# BQ_chip.net
KiCad netlist of a schematic drawn in Altium Designer
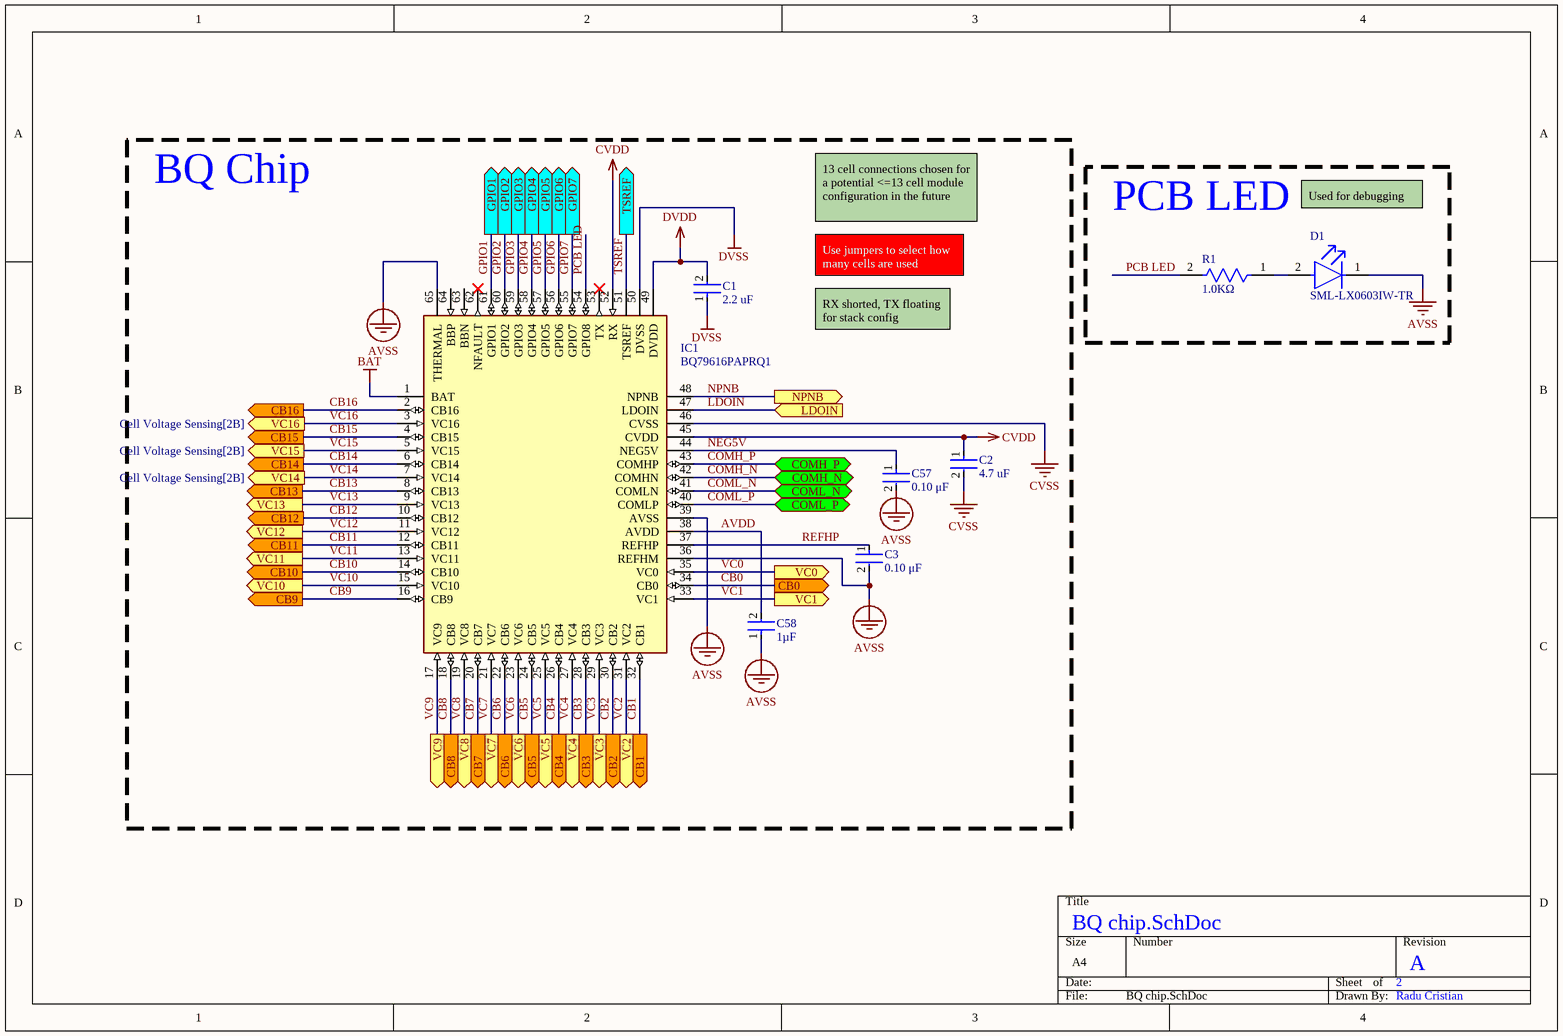
[diagram p0: BQ chip.SchDoc]

(export (version "E")
  (design (tool "Eeschema 10.0.6"))
  (components
    (comp (ref "C1")
      (value "CC0603KPX7R6BB225")
      (footprint "FP-CC0603-DA-MFG")
      (description "CC0603 2.2 uF X7R 10.00% 10 V")
      (fields
        (field (name "OCTOPART") "https://octopart.com/cc0603kpx7r6bb225-yageo-88116733")
        (field (name "TOLERANCE") "0.1")
        (field (name "CAPACITANCE") "2.2 uF")
      )
      (libsource (lib "Altium Content Vault") (part "11868f565c42a9108669ba33697ecf6"))
    )
    (comp (ref "C2")
      (value "CC0603KRX5R7BB475")
      (footprint "FP-CC0603-DA-MFG")
      (description "CAP CER 4.7UF 16V X5R 0603")
      (fields
        (field (name "MANUFACTURER") "YAGEO")
        (field (name "VOLTAGE") "16 V")
        (field (name "CAPACITANCE") "4.7 uF")
      )
      (libsource (lib "Altium Content Vault") (part "11868f565c42a9108669ba33697ecf6"))
    )
    (comp (ref "C3")
      (value "0.10 μF")
      (footprint "FP-C0603C-CF-MFG")
      (description "C0603 0.10 μF X7R 30ppm/°C 5.00% 50 V")
      (fields
        (field (name "MANUFACTURER") "KEMET")
        (field (name "MANUFACTURER PART NUMBER") "C0603C104J5RAC")
      )
      (libsource (lib "Altium Content Vault") (part "b4654b650e69147ec39a6b967a45e02"))
    )
    (comp (ref "C57")
      (value "0.10 μF")
      (footprint "FP-C0603C-CF-MFG")
      (description "C0603 0.10 μF X7R 30ppm/°C 5.00% 50 V")
      (fields
        (field (name "MANUFACTURER") "KEMET")
        (field (name "MANUFACTURER PART NUMBER") "C0603C104J5RAC")
      )
      (libsource (lib "Altium Content Vault") (part "b4654b650e69147ec39a6b967a45e02"))
    )
    (comp (ref "C58")
      (value "VJ0603Y105KXJCW1BC")
      (footprint "FP-VJ0603Y105KXJCW1BC-MFG")
      (description "VJ0603Y105KXJCW1BC Multilayer Ceramic Capacitor, 1 uF, 16 V, ± 10%, X7R, 0603 [1608 Metric]")
      (fields (field (name "CAPACITANCE") "1µF") (field (name "TOLERANCE") "10%"))
      (libsource (lib "Altium Content Vault") (part "b4654b650e69147ec39a6b967a45e02"))
    )
    (comp (ref "D1")
      (value "SML-LX0603IW-TR")
      (footprint "FP-SML-LX0603IW-TR-MFG")
      (description "LED RED DIFFUSED SMD")
      (libsource (lib "Altium Content Vault") (part "8706943c75ba83719d021d2fdc84c58"))
    )
    (comp (ref "IC1")
      (value "BQ79616PAPRQ1")
      (footprint "PcbLib1:QFP50P1200X1200X120-65N")
      (fields (field (name "MOUSER PART NUMBER") "595-BQ79616PAPRQ1"))
      (libsource (lib "Schlib1") (part "BQ79616PAPRQ1"))
    )
    (comp (ref "R1")
      (value "CPF0603F1K0C1")
      (footprint "FP-CPF0603-MFG")
      (description "RES SMD 1.0KΩ 1% 1/16W 0603")
      (fields
        (field (name "OCTOPART") "https://octopart.com/cpf0603f1k0c1-te+connectivity-42013134")
        (field (name "TOLERANCE") "1%")
        (field (name "RESISTANCE") "1.0KΩ")
      )
      (libsource (lib "Altium Content Vault") (part "1029c3af85768c4190bb7ad29bc67b5"))
    )
  )
  (nets
    (net (code "1") (name "/AVDD") (class "Default")
      (node (ref "C58") (pin "2") (pinfunction "2_2") (pintype "passive"))
      (node (ref "IC1") (pin "38") (pinfunction "AVDD_38") (pintype "power_in"))
    )
    (net (code "2") (name "/CB0") (class "Default")
      (node (ref "IC1") (pin "34") (pinfunction "CB0_34") (pintype "bidirectional"))
    )
    (net (code "3") (name "/CB1") (class "Default")
      (node (ref "IC1") (pin "32") (pinfunction "CB1_32") (pintype "bidirectional"))
    )
    (net (code "4") (name "/CB2") (class "Default")
      (node (ref "IC1") (pin "30") (pinfunction "CB2_30") (pintype "bidirectional"))
    )
    (net (code "5") (name "/CB3") (class "Default")
      (node (ref "IC1") (pin "28") (pinfunction "CB3_28") (pintype "bidirectional"))
    )
    (net (code "6") (name "/CB4") (class "Default")
      (node (ref "IC1") (pin "26") (pinfunction "CB4_26") (pintype "bidirectional"))
    )
    (net (code "7") (name "/CB5") (class "Default")
      (node (ref "IC1") (pin "24") (pinfunction "CB5_24") (pintype "bidirectional"))
    )
    (net (code "8") (name "/CB6") (class "Default")
      (node (ref "IC1") (pin "22") (pinfunction "CB6_22") (pintype "bidirectional"))
    )
    (net (code "9") (name "/CB7") (class "Default")
      (node (ref "IC1") (pin "20") (pinfunction "CB7_20") (pintype "bidirectional"))
    )
    (net (code "10") (name "/CB8") (class "Default")
      (node (ref "IC1") (pin "18") (pinfunction "CB8_18") (pintype "bidirectional"))
    )
    (net (code "11") (name "/CB9") (class "Default")
      (node (ref "IC1") (pin "16") (pinfunction "CB9_16") (pintype "bidirectional"))
    )
    (net (code "12") (name "/CB10") (class "Default")
      (node (ref "IC1") (pin "14") (pinfunction "CB10_14") (pintype "bidirectional"))
    )
    (net (code "13") (name "/CB11") (class "Default")
      (node (ref "IC1") (pin "12") (pinfunction "CB11_12") (pintype "bidirectional"))
    )
    (net (code "14") (name "/CB12") (class "Default")
      (node (ref "IC1") (pin "10") (pinfunction "CB12_10") (pintype "bidirectional"))
    )
    (net (code "15") (name "/CB13") (class "Default")
      (node (ref "IC1") (pin "8") (pinfunction "CB13_8") (pintype "bidirectional"))
    )
    (net (code "16") (name "/CB14") (class "Default")
      (node (ref "IC1") (pin "6") (pinfunction "CB14_6") (pintype "bidirectional"))
    )
    (net (code "17") (name "/CB15") (class "Default")
      (node (ref "IC1") (pin "4") (pinfunction "CB15_4") (pintype "bidirectional"))
    )
    (net (code "18") (name "/CB16") (class "Default")
      (node (ref "IC1") (pin "2") (pinfunction "CB16_2") (pintype "bidirectional"))
    )
    (net (code "19") (name "/COMH_N") (class "Default")
      (node (ref "IC1") (pin "42") (pinfunction "COMHN_42") (pintype "bidirectional"))
    )
    (net (code "20") (name "/COMH_P") (class "Default")
      (node (ref "IC1") (pin "43") (pinfunction "COMHP_43") (pintype "bidirectional"))
    )
    (net (code "21") (name "/COML_N") (class "Default")
      (node (ref "IC1") (pin "41") (pinfunction "COMLN_41") (pintype "bidirectional"))
    )
    (net (code "22") (name "/COML_P") (class "Default")
      (node (ref "IC1") (pin "40") (pinfunction "COMLP_40") (pintype "bidirectional"))
    )
    (net (code "23") (name "/GPIO1") (class "Default")
      (node (ref "IC1") (pin "61") (pinfunction "GPIO1_61") (pintype "bidirectional"))
    )
    (net (code "24") (name "/GPIO2") (class "Default")
      (node (ref "IC1") (pin "60") (pinfunction "GPIO2_60") (pintype "bidirectional"))
    )
    (net (code "25") (name "/GPIO3") (class "Default")
      (node (ref "IC1") (pin "59") (pinfunction "GPIO3_59") (pintype "bidirectional"))
    )
    (net (code "26") (name "/GPIO4") (class "Default")
      (node (ref "IC1") (pin "58") (pinfunction "GPIO4_58") (pintype "bidirectional"))
    )
    (net (code "27") (name "/GPIO5") (class "Default")
      (node (ref "IC1") (pin "57") (pinfunction "GPIO5_57") (pintype "bidirectional"))
    )
    (net (code "28") (name "/GPIO6") (class "Default")
      (node (ref "IC1") (pin "56") (pinfunction "GPIO6_56") (pintype "bidirectional"))
    )
    (net (code "29") (name "/GPIO7") (class "Default")
      (node (ref "IC1") (pin "55") (pinfunction "GPIO7_55") (pintype "bidirectional"))
    )
    (net (code "30") (name "/LDOIN") (class "Default")
      (node (ref "IC1") (pin "47") (pinfunction "LDOIN_47") (pintype "power_in"))
    )
    (net (code "31") (name "/NEG5V") (class "Default")
      (node (ref "C57") (pin "1") (pinfunction "1_1") (pintype "passive"))
      (node (ref "IC1") (pin "44") (pinfunction "NEG5V_44") (pintype "power_in"))
    )
    (net (code "32") (name "/NPNB") (class "Default")
      (node (ref "IC1") (pin "48") (pinfunction "NPNB_48") (pintype "power_in"))
    )
    (net (code "33") (name "/PCB LED") (class "Default")
      (node (ref "IC1") (pin "54") (pinfunction "GPIO8_54") (pintype "bidirectional"))
      (node (ref "R1") (pin "2") (pinfunction "2_2") (pintype "passive"))
    )
    (net (code "34") (name "/REFHP") (class "Default")
      (node (ref "C3") (pin "1") (pinfunction "1_1") (pintype "passive"))
      (node (ref "IC1") (pin "37") (pinfunction "REFHP_37") (pintype "power_in"))
    )
    (net (code "35") (name "/TSREF") (class "Default")
      (node (ref "IC1") (pin "51") (pinfunction "TSREF_51") (pintype "power_in"))
    )
    (net (code "36") (name "/VC0") (class "Default")
      (node (ref "IC1") (pin "35") (pinfunction "VC0_35") (pintype "input"))
    )
    (net (code "37") (name "/VC1") (class "Default")
      (node (ref "IC1") (pin "33") (pinfunction "VC1_33") (pintype "input"))
    )
    (net (code "38") (name "/VC2") (class "Default")
      (node (ref "IC1") (pin "31") (pinfunction "VC2_31") (pintype "input"))
    )
    (net (code "39") (name "/VC3") (class "Default")
      (node (ref "IC1") (pin "29") (pinfunction "VC3_29") (pintype "input"))
    )
    (net (code "40") (name "/VC4") (class "Default")
      (node (ref "IC1") (pin "27") (pinfunction "VC4_27") (pintype "input"))
    )
    (net (code "41") (name "/VC5") (class "Default")
      (node (ref "IC1") (pin "25") (pinfunction "VC5_25") (pintype "input"))
    )
    (net (code "42") (name "/VC6") (class "Default")
      (node (ref "IC1") (pin "23") (pinfunction "VC6_23") (pintype "input"))
    )
    (net (code "43") (name "/VC7") (class "Default")
      (node (ref "IC1") (pin "21") (pinfunction "VC7_21") (pintype "input"))
    )
    (net (code "44") (name "/VC8") (class "Default")
      (node (ref "IC1") (pin "19") (pinfunction "VC8_19") (pintype "input"))
    )
    (net (code "45") (name "/VC9") (class "Default")
      (node (ref "IC1") (pin "17") (pinfunction "VC9_17") (pintype "input"))
    )
    (net (code "46") (name "/VC10") (class "Default")
      (node (ref "IC1") (pin "15") (pinfunction "VC10_15") (pintype "input"))
    )
    (net (code "47") (name "/VC11") (class "Default")
      (node (ref "IC1") (pin "13") (pinfunction "VC11_13") (pintype "input"))
    )
    (net (code "48") (name "/VC12") (class "Default")
      (node (ref "IC1") (pin "11") (pinfunction "VC12_11") (pintype "input"))
    )
    (net (code "49") (name "/VC13") (class "Default")
      (node (ref "IC1") (pin "9") (pinfunction "VC13_9") (pintype "input"))
    )
    (net (code "50") (name "/VC14") (class "Default")
      (node (ref "IC1") (pin "7") (pinfunction "VC14_7") (pintype "input"))
    )
    (net (code "51") (name "/VC15") (class "Default")
      (node (ref "IC1") (pin "5") (pinfunction "VC15_5") (pintype "input"))
    )
    (net (code "52") (name "/VC16") (class "Default")
      (node (ref "IC1") (pin "3") (pinfunction "VC16_3") (pintype "input"))
    )
    (net (code "53") (name "AVSS") (class "Default")
      (node (ref "C3") (pin "2") (pinfunction "2_2") (pintype "passive"))
      (node (ref "C57") (pin "2") (pinfunction "2_2") (pintype "passive"))
      (node (ref "C58") (pin "1") (pinfunction "1_1") (pintype "passive"))
      (node (ref "D1") (pin "1") (pinfunction "C_1") (pintype "passive"))
      (node (ref "IC1") (pin "36") (pinfunction "REFHM_36") (pintype "power_in"))
      (node (ref "IC1") (pin "39") (pinfunction "AVSS_39") (pintype "power_in"))
      (node (ref "IC1") (pin "65") (pinfunction "THERMAL_65") (pintype "passive"))
    )
    (net (code "54") (name "BAT") (class "Default")
      (node (ref "IC1") (pin "1") (pinfunction "BAT_1") (pintype "power_in"))
    )
    (net (code "55") (name "CVDD") (class "Default")
      (node (ref "C2") (pin "1") (pinfunction "1_1") (pintype "passive"))
      (node (ref "IC1") (pin "45") (pinfunction "CVDD_45") (pintype "power_in"))
      (node (ref "IC1") (pin "52") (pinfunction "RX_52") (pintype "input"))
    )
    (net (code "56") (name "CVSS") (class "Default")
      (node (ref "C2") (pin "2") (pinfunction "2_2") (pintype "passive"))
      (node (ref "IC1") (pin "46") (pinfunction "CVSS_46") (pintype "power_in"))
    )
    (net (code "57") (name "DVDD") (class "Default")
      (node (ref "C1") (pin "2") (pinfunction "2_2") (pintype "passive"))
      (node (ref "IC1") (pin "49") (pinfunction "DVDD_49") (pintype "power_in"))
    )
    (net (code "58") (name "DVSS") (class "Default")
      (node (ref "C1") (pin "1") (pinfunction "1_1") (pintype "passive"))
      (node (ref "IC1") (pin "50") (pinfunction "DVSS_50") (pintype "power_in"))
    )
    (net (code "59") (name "Net-(D1-A)") (class "Default")
      (node (ref "D1") (pin "2") (pinfunction "A_2") (pintype "passive"))
      (node (ref "R1") (pin "1") (pinfunction "1_1") (pintype "passive"))
    )
    (net (code "60") (name "unconnected-(IC1-BBN-Pad63)") (class "Default")
      (node (ref "IC1") (pin "63") (pinfunction "BBN_63") (pintype "input"))
    )
    (net (code "61") (name "unconnected-(IC1-BBP-Pad64)") (class "Default")
      (node (ref "IC1") (pin "64") (pinfunction "BBP_64") (pintype "input"))
    )
    (net (code "62") (name "unconnected-(IC1-NFAULT-Pad62)") (class "Default")
      (node (ref "IC1") (pin "62") (pinfunction "NFAULT_62") (pintype "output+no_connect"))
    )
    (net (code "63") (name "unconnected-(IC1-TX-Pad53)") (class "Default")
      (node (ref "IC1") (pin "53") (pinfunction "TX_53") (pintype "output+no_connect"))
    )
  )
)
